# Amplifier.net
KiCad netlist of a schematic drawn in EAGLE
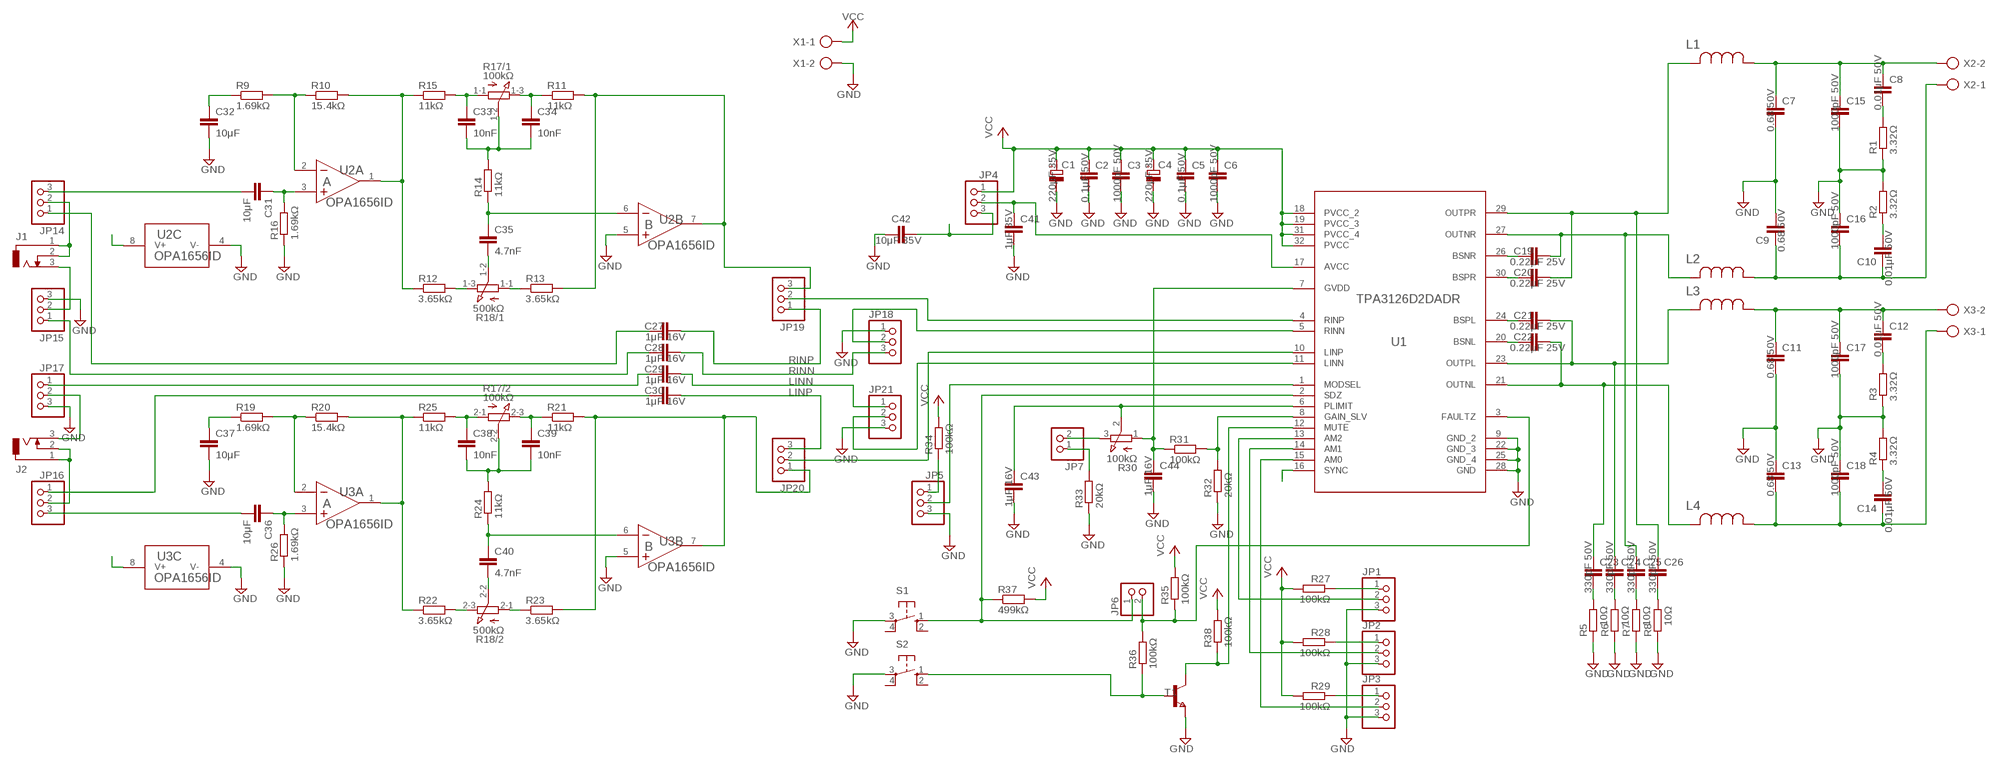
[diagram p0: schematic, sheet 1]

(export (version "E")
  (design (tool "Eeschema 10.0.6"))
  (components
    (comp (ref "C1")
      (value "220μF 35V")
      (footprint "eagle-import:E3,5-10")
      (libsource (lib "eagle-import") (part "CPOL-EUE3.5-10"))
    )
    (comp (ref "C2")
      (value "0.1μF 50V")
      (footprint "eagle-import:C0805")
      (libsource (lib "eagle-import") (part "C-EUC0805"))
    )
    (comp (ref "C3")
      (value "1000pF 50V")
      (footprint "eagle-import:C0805")
      (libsource (lib "eagle-import") (part "C-EUC0805"))
    )
    (comp (ref "C4")
      (value "220μF 35V")
      (footprint "eagle-import:E3,5-10")
      (libsource (lib "eagle-import") (part "CPOL-EUE3.5-10"))
    )
    (comp (ref "C5")
      (value "0.1μF 50V")
      (footprint "eagle-import:C0805")
      (libsource (lib "eagle-import") (part "C-EUC0805"))
    )
    (comp (ref "C6")
      (value "1000pF 50V")
      (footprint "eagle-import:C0805")
      (libsource (lib "eagle-import") (part "C-EUC0805"))
    )
    (comp (ref "C7")
      (value "0.68 50V")
      (footprint "eagle-import:C0805")
      (libsource (lib "eagle-import") (part "C-EUC0805"))
    )
    (comp (ref "C8")
      (value "0.01μF 50V")
      (footprint "eagle-import:C0805")
      (libsource (lib "eagle-import") (part "C-EUC0805"))
    )
    (comp (ref "C9")
      (value "0.68 50V")
      (footprint "eagle-import:C0805")
      (libsource (lib "eagle-import") (part "C-EUC0805"))
    )
    (comp (ref "C10")
      (value "0.01μF 50V")
      (footprint "eagle-import:C0805")
      (libsource (lib "eagle-import") (part "C-EUC0805"))
    )
    (comp (ref "C11")
      (value "0.68 50V")
      (footprint "eagle-import:C0805")
      (libsource (lib "eagle-import") (part "C-EUC0805"))
    )
    (comp (ref "C12")
      (value "0.01μF 50V")
      (footprint "eagle-import:C0805")
      (libsource (lib "eagle-import") (part "C-EUC0805"))
    )
    (comp (ref "C13")
      (value "0.68 50V")
      (footprint "eagle-import:C0805")
      (libsource (lib "eagle-import") (part "C-EUC0805"))
    )
    (comp (ref "C14")
      (value "0.01μF 50V")
      (footprint "eagle-import:C0805")
      (libsource (lib "eagle-import") (part "C-EUC0805"))
    )
    (comp (ref "C15")
      (value "1000pF 50V")
      (footprint "eagle-import:C0603")
      (libsource (lib "eagle-import") (part "C-EUC0603"))
    )
    (comp (ref "C16")
      (value "1000pF 50V")
      (footprint "eagle-import:C0603")
      (libsource (lib "eagle-import") (part "C-EUC0603"))
    )
    (comp (ref "C17")
      (value "1000pF 50V")
      (footprint "eagle-import:C0603")
      (libsource (lib "eagle-import") (part "C-EUC0603"))
    )
    (comp (ref "C18")
      (value "1000pF 50V")
      (footprint "eagle-import:C0603")
      (libsource (lib "eagle-import") (part "C-EUC0603"))
    )
    (comp (ref "C19")
      (value "0.22μF 25V")
      (footprint "eagle-import:C0603")
      (libsource (lib "eagle-import") (part "C-EUC0603"))
    )
    (comp (ref "C20")
      (value "0.22μF 25V")
      (footprint "eagle-import:C0603")
      (libsource (lib "eagle-import") (part "C-EUC0603"))
    )
    (comp (ref "C21")
      (value "0.22μF 25V")
      (footprint "eagle-import:C0603")
      (libsource (lib "eagle-import") (part "C-EUC0603"))
    )
    (comp (ref "C22")
      (value "0.22μF 25V")
      (footprint "eagle-import:C0603")
      (libsource (lib "eagle-import") (part "C-EUC0603"))
    )
    (comp (ref "C23")
      (value "330pF 50V")
      (footprint "eagle-import:C0603")
      (libsource (lib "eagle-import") (part "C-EUC0603"))
    )
    (comp (ref "C24")
      (value "330pF 50V")
      (footprint "eagle-import:C0603")
      (libsource (lib "eagle-import") (part "C-EUC0603"))
    )
    (comp (ref "C25")
      (value "330pF 50V")
      (footprint "eagle-import:C0603")
      (libsource (lib "eagle-import") (part "C-EUC0603"))
    )
    (comp (ref "C26")
      (value "330pF 50V")
      (footprint "eagle-import:C0603")
      (libsource (lib "eagle-import") (part "C-EUC0603"))
    )
    (comp (ref "C27")
      (value "1μF 16V")
      (footprint "eagle-import:C0805")
      (libsource (lib "eagle-import") (part "C-EUC0805"))
    )
    (comp (ref "C28")
      (value "1μF 16V")
      (footprint "eagle-import:C0805")
      (libsource (lib "eagle-import") (part "C-EUC0805"))
    )
    (comp (ref "C29")
      (value "1μF 16V")
      (footprint "eagle-import:C0805")
      (libsource (lib "eagle-import") (part "C-EUC0805"))
    )
    (comp (ref "C30")
      (value "1μF 16V")
      (footprint "eagle-import:C0805")
      (libsource (lib "eagle-import") (part "C-EUC0805"))
    )
    (comp (ref "C31")
      (value "10μF")
      (footprint "eagle-import:C0805")
      (libsource (lib "eagle-import") (part "C-EUC0805"))
    )
    (comp (ref "C32")
      (value "10μF")
      (footprint "eagle-import:C0805")
      (libsource (lib "eagle-import") (part "C-EUC0805"))
    )
    (comp (ref "C33")
      (value "10nF")
      (footprint "eagle-import:C0603")
      (libsource (lib "eagle-import") (part "C-EUC0603"))
    )
    (comp (ref "C34")
      (value "10nF")
      (footprint "eagle-import:C0603")
      (libsource (lib "eagle-import") (part "C-EUC0603"))
    )
    (comp (ref "C35")
      (value "4.7nF")
      (footprint "eagle-import:C0603")
      (libsource (lib "eagle-import") (part "C-EUC0603"))
    )
    (comp (ref "C36")
      (value "10μF")
      (footprint "eagle-import:C0805")
      (libsource (lib "eagle-import") (part "C-EUC0805"))
    )
    (comp (ref "C37")
      (value "10μF")
      (footprint "eagle-import:C0805")
      (libsource (lib "eagle-import") (part "C-EUC0805"))
    )
    (comp (ref "C38")
      (value "10nF")
      (footprint "eagle-import:C0603")
      (libsource (lib "eagle-import") (part "C-EUC0603"))
    )
    (comp (ref "C39")
      (value "10nF")
      (footprint "eagle-import:C0603")
      (libsource (lib "eagle-import") (part "C-EUC0603"))
    )
    (comp (ref "C40")
      (value "4.7nF")
      (footprint "eagle-import:C0603")
      (libsource (lib "eagle-import") (part "C-EUC0603"))
    )
    (comp (ref "C41")
      (value "1μF 35V")
      (footprint "eagle-import:C0603")
      (libsource (lib "eagle-import") (part "C-EUC0603"))
    )
    (comp (ref "C42")
      (value "10μF 35V")
      (footprint "eagle-import:C1210")
      (libsource (lib "eagle-import") (part "C-EUC1210"))
    )
    (comp (ref "C43")
      (value "1μF 16V")
      (footprint "eagle-import:C0805")
      (libsource (lib "eagle-import") (part "C-EUC0805"))
    )
    (comp (ref "C44")
      (value "1μF 16V")
      (footprint "eagle-import:C0805")
      (libsource (lib "eagle-import") (part "C-EUC0805"))
    )
    (comp (ref "J1")
      (value "DCJ0303")
      (footprint "eagle-import:DCJ0303")
      (libsource (lib "eagle-import") (part "DCJ0303"))
    )
    (comp (ref "J2")
      (value "DCJ0303")
      (footprint "eagle-import:DCJ0303")
      (libsource (lib "eagle-import") (part "DCJ0303"))
    )
    (comp (ref "JP1")
      (value "PINHD-1X3")
      (footprint "eagle-import:1X03")
      (libsource (lib "eagle-import") (part "PINHD-1X3"))
    )
    (comp (ref "JP2")
      (value "PINHD-1X3")
      (footprint "eagle-import:1X03")
      (libsource (lib "eagle-import") (part "PINHD-1X3"))
    )
    (comp (ref "JP3")
      (value "PINHD-1X3")
      (footprint "eagle-import:1X03")
      (libsource (lib "eagle-import") (part "PINHD-1X3"))
    )
    (comp (ref "JP4")
      (value "PINHD-1X3")
      (footprint "eagle-import:1X03")
      (libsource (lib "eagle-import") (part "PINHD-1X3"))
    )
    (comp (ref "JP5")
      (value "PINHD-1X3")
      (footprint "eagle-import:1X03")
      (libsource (lib "eagle-import") (part "PINHD-1X3"))
    )
    (comp (ref "JP6")
      (value "PINHD-1X2")
      (footprint "eagle-import:1X02")
      (libsource (lib "eagle-import") (part "PINHD-1X2"))
    )
    (comp (ref "JP7")
      (value "PINHD-1X2")
      (footprint "eagle-import:1X02")
      (libsource (lib "eagle-import") (part "PINHD-1X2"))
    )
    (comp (ref "JP14")
      (value "PINHD-1X3")
      (footprint "eagle-import:1X03")
      (libsource (lib "eagle-import") (part "PINHD-1X3"))
    )
    (comp (ref "JP15")
      (value "PINHD-1X3")
      (footprint "eagle-import:1X03")
      (libsource (lib "eagle-import") (part "PINHD-1X3"))
    )
    (comp (ref "JP16")
      (value "PINHD-1X3")
      (footprint "eagle-import:1X03")
      (libsource (lib "eagle-import") (part "PINHD-1X3"))
    )
    (comp (ref "JP17")
      (value "PINHD-1X3")
      (footprint "eagle-import:1X03")
      (libsource (lib "eagle-import") (part "PINHD-1X3"))
    )
    (comp (ref "JP18")
      (value "PINHD-1X3")
      (footprint "eagle-import:1X03")
      (libsource (lib "eagle-import") (part "PINHD-1X3"))
    )
    (comp (ref "JP19")
      (value "PINHD-1X3")
      (footprint "eagle-import:1X03")
      (libsource (lib "eagle-import") (part "PINHD-1X3"))
    )
    (comp (ref "JP20")
      (value "PINHD-1X3")
      (footprint "eagle-import:1X03")
      (libsource (lib "eagle-import") (part "PINHD-1X3"))
    )
    (comp (ref "JP21")
      (value "PINHD-1X3")
      (footprint "eagle-import:1X03")
      (libsource (lib "eagle-import") (part "PINHD-1X3"))
    )
    (comp (ref "L1")
      (value "7447709100")
      (footprint "eagle-import:IND_1210-WE-PD_WRE")
      (fields (field (name "COPYRIGHT") "Copyright (C) 2023 Ultra Librarian. All rights reserved."))
      (libsource (lib "eagle-import") (part "7447709100"))
    )
    (comp (ref "L2")
      (value "7447709100")
      (footprint "eagle-import:IND_1210-WE-PD_WRE")
      (fields (field (name "COPYRIGHT") "Copyright (C) 2023 Ultra Librarian. All rights reserved."))
      (libsource (lib "eagle-import") (part "7447709100"))
    )
    (comp (ref "L3")
      (value "7447709100")
      (footprint "eagle-import:IND_1210-WE-PD_WRE")
      (fields (field (name "COPYRIGHT") "Copyright (C) 2023 Ultra Librarian. All rights reserved."))
      (libsource (lib "eagle-import") (part "7447709100"))
    )
    (comp (ref "L4")
      (value "7447709100")
      (footprint "eagle-import:IND_1210-WE-PD_WRE")
      (fields (field (name "COPYRIGHT") "Copyright (C) 2023 Ultra Librarian. All rights reserved."))
      (libsource (lib "eagle-import") (part "7447709100"))
    )
    (comp (ref "R1")
      (value "3.32Ω")
      (footprint "eagle-import:R0603")
      (libsource (lib "eagle-import") (part "R-EU_R0603"))
    )
    (comp (ref "R2")
      (value "3.32Ω")
      (footprint "eagle-import:R0603")
      (libsource (lib "eagle-import") (part "R-EU_R0603"))
    )
    (comp (ref "R3")
      (value "3.32Ω")
      (footprint "eagle-import:R0603")
      (libsource (lib "eagle-import") (part "R-EU_R0603"))
    )
    (comp (ref "R4")
      (value "3.32Ω")
      (footprint "eagle-import:R0603")
      (libsource (lib "eagle-import") (part "R-EU_R0603"))
    )
    (comp (ref "R5")
      (value "10Ω")
      (footprint "eagle-import:R0805")
      (libsource (lib "eagle-import") (part "R-EU_R0805"))
    )
    (comp (ref "R6")
      (value "10Ω")
      (footprint "eagle-import:R0805")
      (libsource (lib "eagle-import") (part "R-EU_R0805"))
    )
    (comp (ref "R7")
      (value "10Ω")
      (footprint "eagle-import:R0805")
      (libsource (lib "eagle-import") (part "R-EU_R0805"))
    )
    (comp (ref "R8")
      (value "10Ω")
      (footprint "eagle-import:R0805")
      (libsource (lib "eagle-import") (part "R-EU_R0805"))
    )
    (comp (ref "R9")
      (value "1.69kΩ")
      (footprint "eagle-import:R1206")
      (libsource (lib "eagle-import") (part "R-EU_R1206"))
    )
    (comp (ref "R10")
      (value "15.4kΩ")
      (footprint "eagle-import:R1206")
      (libsource (lib "eagle-import") (part "R-EU_R1206"))
    )
    (comp (ref "R11")
      (value "11kΩ")
      (footprint "eagle-import:R1206")
      (libsource (lib "eagle-import") (part "R-EU_R1206"))
    )
    (comp (ref "R12")
      (value "3.65kΩ")
      (footprint "eagle-import:R1206")
      (libsource (lib "eagle-import") (part "R-EU_R1206"))
    )
    (comp (ref "R13")
      (value "3.65kΩ")
      (footprint "eagle-import:R1206")
      (libsource (lib "eagle-import") (part "R-EU_R1206"))
    )
    (comp (ref "R14")
      (value "11kΩ")
      (footprint "eagle-import:R1206")
      (libsource (lib "eagle-import") (part "R-EU_R1206"))
    )
    (comp (ref "R15")
      (value "11kΩ")
      (footprint "eagle-import:R1206")
      (libsource (lib "eagle-import") (part "R-EU_R1206"))
    )
    (comp (ref "R16")
      (value "1.69kΩ")
      (footprint "eagle-import:R1206")
      (libsource (lib "eagle-import") (part "R-EU_R1206"))
    )
    (comp (ref "R17")
      (value "100kΩ")
      (footprint "eagle-import:3RP_1610G")
      (libsource (lib "eagle-import") (part "3RP/1610G"))
    )
    (comp (ref "R18")
      (value "500kΩ")
      (footprint "eagle-import:3RP_1610G")
      (libsource (lib "eagle-import") (part "3RP/1610G"))
    )
    (comp (ref "R19")
      (value "1.69kΩ")
      (footprint "eagle-import:R1206")
      (libsource (lib "eagle-import") (part "R-EU_R1206"))
    )
    (comp (ref "R20")
      (value "15.4kΩ")
      (footprint "eagle-import:R1206")
      (libsource (lib "eagle-import") (part "R-EU_R1206"))
    )
    (comp (ref "R21")
      (value "11kΩ")
      (footprint "eagle-import:R1206")
      (libsource (lib "eagle-import") (part "R-EU_R1206"))
    )
    (comp (ref "R22")
      (value "3.65kΩ")
      (footprint "eagle-import:R1206")
      (libsource (lib "eagle-import") (part "R-EU_R1206"))
    )
    (comp (ref "R23")
      (value "3.65kΩ")
      (footprint "eagle-import:R1206")
      (libsource (lib "eagle-import") (part "R-EU_R1206"))
    )
    (comp (ref "R24")
      (value "11kΩ")
      (footprint "eagle-import:R1206")
      (libsource (lib "eagle-import") (part "R-EU_R1206"))
    )
    (comp (ref "R25")
      (value "11kΩ")
      (footprint "eagle-import:R1206")
      (libsource (lib "eagle-import") (part "R-EU_R1206"))
    )
    (comp (ref "R26")
      (value "1.69kΩ")
      (footprint "eagle-import:R1206")
      (libsource (lib "eagle-import") (part "R-EU_R1206"))
    )
    (comp (ref "R27")
      (value "100kΩ")
      (footprint "eagle-import:M0805")
      (libsource (lib "eagle-import") (part "R-EU_M0805"))
    )
    (comp (ref "R28")
      (value "100kΩ")
      (footprint "eagle-import:M0805")
      (libsource (lib "eagle-import") (part "R-EU_M0805"))
    )
    (comp (ref "R29")
      (value "100kΩ")
      (footprint "eagle-import:M0805")
      (libsource (lib "eagle-import") (part "R-EU_M0805"))
    )
    (comp (ref "R30")
      (value "100kΩ")
      (footprint "eagle-import:3RP_1610N")
      (libsource (lib "eagle-import") (part "3RP/1610N"))
    )
    (comp (ref "R31")
      (value "100kΩ")
      (footprint "eagle-import:R0805")
      (libsource (lib "eagle-import") (part "R-EU_R0805"))
    )
    (comp (ref "R32")
      (value "20kΩ")
      (footprint "eagle-import:R0805")
      (libsource (lib "eagle-import") (part "R-EU_R0805"))
    )
    (comp (ref "R33")
      (value "20kΩ")
      (footprint "eagle-import:R0805")
      (libsource (lib "eagle-import") (part "R-EU_R0805"))
    )
    (comp (ref "R34")
      (value "100kΩ")
      (footprint "eagle-import:R0805")
      (libsource (lib "eagle-import") (part "R-EU_R0805"))
    )
    (comp (ref "R35")
      (value "100kΩ")
      (footprint "eagle-import:R0805")
      (libsource (lib "eagle-import") (part "R-EU_R0805"))
    )
    (comp (ref "R36")
      (value "100kΩ")
      (footprint "eagle-import:R0805")
      (libsource (lib "eagle-import") (part "R-EU_R0805"))
    )
    (comp (ref "R37")
      (value "499kΩ")
      (footprint "eagle-import:R0805")
      (libsource (lib "eagle-import") (part "R-EU_R0805"))
    )
    (comp (ref "R38")
      (value "100kΩ")
      (footprint "eagle-import:R0805")
      (libsource (lib "eagle-import") (part "R-EU_R0805"))
    )
    (comp (ref "S1")
      (value "10-XX")
      (footprint "eagle-import:B3F-10XX")
      (fields (field (name "MPN") "B3F-1000"))
      (libsource (lib "eagle-import") (part "10-XX"))
    )
    (comp (ref "S2")
      (value "10-XX")
      (footprint "eagle-import:B3F-10XX")
      (fields (field (name "MPN") "B3F-1000"))
      (libsource (lib "eagle-import") (part "10-XX"))
    )
    (comp (ref "T1")
      (value "NPNSOT23")
      (footprint "eagle-import:SOT-23")
      (fields (field (name "MPN") "DSS20201L-7"))
      (libsource (lib "eagle-import") (part "NPNSOT23"))
    )
    (comp (ref "U1")
      (value "TPA3126D2DADR")
      (footprint "eagle-import:DAD0032A_N")
      (fields (field (name "COPYRIGHT") "Copyright (C) 2023 Ultra Librarian. All rights reserved."))
      (libsource (lib "eagle-import") (part "TPA3126D2DADR"))
    )
    (comp (ref "U2")
      (value "OPA1656ID")
      (footprint "eagle-import:D0008A_N")
      (fields (field (name "COPYRIGHT") "Copyright (C) 2023 Ultra Librarian. All rights reserved."))
      (libsource (lib "eagle-import") (part "OPA1656ID"))
    )
    (comp (ref "U3")
      (value "OPA1656ID")
      (footprint "eagle-import:D0008A_N")
      (fields (field (name "COPYRIGHT") "Copyright (C) 2023 Ultra Librarian. All rights reserved."))
      (libsource (lib "eagle-import") (part "OPA1656ID"))
    )
    (comp (ref "X1")
      (value "AK500/2")
      (footprint "eagle-import:AK500_2")
      (libsource (lib "eagle-import") (part "AK500/2"))
    )
    (comp (ref "X2")
      (value "AK500/2")
      (footprint "eagle-import:AK500_2")
      (libsource (lib "eagle-import") (part "AK500/2"))
    )
    (comp (ref "X3")
      (value "AK500/2")
      (footprint "eagle-import:AK500_2")
      (libsource (lib "eagle-import") (part "AK500/2"))
    )
  )
  (nets
    (net (code "1") (name "/LINN") (class "Default")
      (node (ref "C29") (pin "2") (pinfunction "2_2") (pintype "passive"))
      (node (ref "JP21") (pin "1") (pinfunction "1_1") (pintype "passive"))
    )
    (net (code "2") (name "/LINP") (class "Default")
      (node (ref "C30") (pin "1") (pinfunction "1_1") (pintype "passive"))
      (node (ref "C30") (pin "2") (pinfunction "2_2") (pintype "passive"))
      (node (ref "JP16") (pin "1") (pinfunction "1_1") (pintype "passive"))
      (node (ref "JP20") (pin "3") (pinfunction "3_3") (pintype "passive"))
    )
    (net (code "3") (name "/RINN") (class "Default")
      (node (ref "C28") (pin "1") (pinfunction "1_1") (pintype "passive"))
      (node (ref "C28") (pin "2") (pinfunction "2_2") (pintype "passive"))
      (node (ref "JP15") (pin "1") (pinfunction "1_1") (pintype "passive"))
      (node (ref "JP18") (pin "3") (pinfunction "3_3") (pintype "passive"))
    )
    (net (code "4") (name "/RINP") (class "Default")
      (node (ref "C27") (pin "1") (pinfunction "1_1") (pintype "passive"))
      (node (ref "C27") (pin "2") (pinfunction "2_2") (pintype "passive"))
      (node (ref "JP14") (pin "1") (pinfunction "1_1") (pintype "passive"))
      (node (ref "JP19") (pin "1") (pinfunction "1_1") (pintype "passive"))
    )
    (net (code "5") (name "GND") (class "Default")
      (node (ref "C1") (pin "-") (pinfunction "-_-") (pintype "passive"))
      (node (ref "C11") (pin "2") (pinfunction "2_2") (pintype "passive"))
      (node (ref "C13") (pin "1") (pinfunction "1_1") (pintype "passive"))
      (node (ref "C15") (pin "2") (pinfunction "2_2") (pintype "passive"))
      (node (ref "C16") (pin "1") (pinfunction "1_1") (pintype "passive"))
      (node (ref "C17") (pin "2") (pinfunction "2_2") (pintype "passive"))
      (node (ref "C18") (pin "1") (pinfunction "1_1") (pintype "passive"))
      (node (ref "C2") (pin "2") (pinfunction "2_2") (pintype "passive"))
      (node (ref "C3") (pin "2") (pinfunction "2_2") (pintype "passive"))
      (node (ref "C32") (pin "2") (pinfunction "2_2") (pintype "passive"))
      (node (ref "C37") (pin "2") (pinfunction "2_2") (pintype "passive"))
      (node (ref "C4") (pin "-") (pinfunction "-_-") (pintype "passive"))
      (node (ref "C41") (pin "2") (pinfunction "2_2") (pintype "passive"))
      (node (ref "C42") (pin "1") (pinfunction "1_1") (pintype "passive"))
      (node (ref "C43") (pin "2") (pinfunction "2_2") (pintype "passive"))
      (node (ref "C44") (pin "2") (pinfunction "2_2") (pintype "passive"))
      (node (ref "C5") (pin "2") (pinfunction "2_2") (pintype "passive"))
      (node (ref "C6") (pin "2") (pinfunction "2_2") (pintype "passive"))
      (node (ref "C7") (pin "2") (pinfunction "2_2") (pintype "passive"))
      (node (ref "C9") (pin "2") (pinfunction "2_2") (pintype "passive"))
      (node (ref "JP1") (pin "3") (pinfunction "3_3") (pintype "passive"))
      (node (ref "JP15") (pin "3") (pinfunction "3_3") (pintype "passive"))
      (node (ref "JP17") (pin "3") (pinfunction "3_3") (pintype "passive"))
      (node (ref "JP18") (pin "1") (pinfunction "1_1") (pintype "passive"))
      (node (ref "JP2") (pin "3") (pinfunction "3_3") (pintype "passive"))
      (node (ref "JP21") (pin "3") (pinfunction "3_3") (pintype "passive"))
      (node (ref "JP3") (pin "3") (pinfunction "3_3") (pintype "passive"))
      (node (ref "JP5") (pin "3") (pinfunction "3_3") (pintype "passive"))
      (node (ref "R1") (pin "1") (pinfunction "1_1") (pintype "passive"))
      (node (ref "R16") (pin "1") (pinfunction "1_1") (pintype "passive"))
      (node (ref "R2") (pin "2") (pinfunction "2_2") (pintype "passive"))
      (node (ref "R26") (pin "1") (pinfunction "1_1") (pintype "passive"))
      (node (ref "R3") (pin "1") (pinfunction "1_1") (pintype "passive"))
      (node (ref "R32") (pin "1") (pinfunction "1_1") (pintype "passive"))
      (node (ref "R33") (pin "1") (pinfunction "1_1") (pintype "passive"))
      (node (ref "R4") (pin "2") (pinfunction "2_2") (pintype "passive"))
      (node (ref "R5") (pin "1") (pinfunction "1_1") (pintype "passive"))
      (node (ref "R6") (pin "1") (pinfunction "1_1") (pintype "passive"))
      (node (ref "R7") (pin "1") (pinfunction "1_1") (pintype "passive"))
      (node (ref "R8") (pin "1") (pinfunction "1_1") (pintype "passive"))
      (node (ref "S1") (pin "3") (pinfunction "P_3") (pintype "passive"))
      (node (ref "S2") (pin "3") (pinfunction "P_3") (pintype "passive"))
      (node (ref "T1") (pin "2") (pinfunction "E_2") (pintype "passive"))
      (node (ref "U1") (pin "22") (pinfunction "GND_3_22") (pintype "power_in"))
      (node (ref "U1") (pin "25") (pinfunction "GND_4_25") (pintype "power_in"))
      (node (ref "U1") (pin "28") (pinfunction "GND_28") (pintype "power_in"))
      (node (ref "U1") (pin "9") (pinfunction "GND_2_9") (pintype "power_in"))
      (node (ref "U2") (pin "4") (pinfunction "V-_4") (pintype "power_in"))
      (node (ref "U2") (pin "5") (pinfunction "IN+_5") (pintype "input"))
      (node (ref "U3") (pin "4") (pinfunction "V-_4") (pintype "power_in"))
      (node (ref "U3") (pin "5") (pinfunction "IN+_5") (pintype "input"))
      (node (ref "X1") (pin "2") (pinfunction "KL_2") (pintype "passive"))
    )
    (net (code "6") (name "Net-(C8-Pad2)") (class "Default")
      (node (ref "C8") (pin "2") (pinfunction "2_2") (pintype "passive"))
      (node (ref "R1") (pin "2") (pinfunction "2_2") (pintype "passive"))
    )
    (net (code "7") (name "Net-(C10-Pad2)") (class "Default")
      (node (ref "C10") (pin "2") (pinfunction "2_2") (pintype "passive"))
      (node (ref "R2") (pin "1") (pinfunction "1_1") (pintype "passive"))
    )
    (net (code "8") (name "Net-(C12-Pad2)") (class "Default")
      (node (ref "C12") (pin "2") (pinfunction "2_2") (pintype "passive"))
      (node (ref "R3") (pin "2") (pinfunction "2_2") (pintype "passive"))
    )
    (net (code "9") (name "Net-(C14-Pad2)") (class "Default")
      (node (ref "C14") (pin "2") (pinfunction "2_2") (pintype "passive"))
      (node (ref "R4") (pin "1") (pinfunction "1_1") (pintype "passive"))
    )
    (net (code "10") (name "Net-(C23-Pad2)") (class "Default")
      (node (ref "C23") (pin "2") (pinfunction "2_2") (pintype "passive"))
      (node (ref "R5") (pin "2") (pinfunction "2_2") (pintype "passive"))
    )
    (net (code "11") (name "Net-(C24-Pad2)") (class "Default")
      (node (ref "C24") (pin "2") (pinfunction "2_2") (pintype "passive"))
      (node (ref "R6") (pin "2") (pinfunction "2_2") (pintype "passive"))
    )
    (net (code "12") (name "Net-(C25-Pad2)") (class "Default")
      (node (ref "C25") (pin "2") (pinfunction "2_2") (pintype "passive"))
      (node (ref "R7") (pin "2") (pinfunction "2_2") (pintype "passive"))
    )
    (net (code "13") (name "Net-(C26-Pad2)") (class "Default")
      (node (ref "C26") (pin "2") (pinfunction "2_2") (pintype "passive"))
      (node (ref "R8") (pin "2") (pinfunction "2_2") (pintype "passive"))
    )
    (net (code "14") (name "Net-(C29-Pad1)") (class "Default")
      (node (ref "C29") (pin "1") (pinfunction "1_1") (pintype "passive"))
      (node (ref "JP17") (pin "1") (pinfunction "1_1") (pintype "passive"))
    )
    (net (code "15") (name "Net-(C31-Pad2)") (class "Default")
      (node (ref "C31") (pin "2") (pinfunction "2_2") (pintype "passive"))
      (node (ref "JP14") (pin "3") (pinfunction "3_3") (pintype "passive"))
    )
    (net (code "16") (name "Net-(C32-Pad1)") (class "Default")
      (node (ref "C32") (pin "1") (pinfunction "1_1") (pintype "passive"))
      (node (ref "R9") (pin "1") (pinfunction "1_1") (pintype "passive"))
    )
    (net (code "17") (name "Net-(C36-Pad2)") (class "Default")
      (node (ref "C36") (pin "2") (pinfunction "2_2") (pintype "passive"))
      (node (ref "JP16") (pin "3") (pinfunction "3_3") (pintype "passive"))
    )
    (net (code "18") (name "Net-(C37-Pad1)") (class "Default")
      (node (ref "C37") (pin "1") (pinfunction "1_1") (pintype "passive"))
      (node (ref "R19") (pin "1") (pinfunction "1_1") (pintype "passive"))
    )
    (net (code "19") (name "Net-(C42-Pad2)") (class "Default")
      (node (ref "C42") (pin "2") (pinfunction "2_2") (pintype "passive"))
      (node (ref "JP4") (pin "3") (pinfunction "3_3") (pintype "passive"))
    )
    (net (code "20") (name "Net-(J1-Pad1)") (class "Default")
      (node (ref "J1") (pin "1") (pinfunction "1_1") (pintype "passive"))
      (node (ref "J1") (pin "2") (pinfunction "2_2") (pintype "passive"))
      (node (ref "JP14") (pin "2") (pinfunction "2_2") (pintype "passive"))
    )
    (net (code "21") (name "Net-(J1-Pad3)") (class "Default")
      (node (ref "J1") (pin "3") (pinfunction "3_3") (pintype "passive"))
      (node (ref "JP15") (pin "2") (pinfunction "2_2") (pintype "passive"))
    )
    (net (code "22") (name "Net-(J2-Pad1)") (class "Default")
      (node (ref "J2") (pin "1") (pinfunction "1_1") (pintype "passive"))
      (node (ref "J2") (pin "2") (pinfunction "2_2") (pintype "passive"))
      (node (ref "JP16") (pin "2") (pinfunction "2_2") (pintype "passive"))
    )
    (net (code "23") (name "Net-(J2-Pad3)") (class "Default")
      (node (ref "J2") (pin "3") (pinfunction "3_3") (pintype "passive"))
      (node (ref "JP17") (pin "2") (pinfunction "2_2") (pintype "passive"))
    )
    (net (code "24") (name "Net-(JP1-Pad1)") (class "Default")
      (node (ref "JP1") (pin "1") (pinfunction "1_1") (pintype "passive"))
      (node (ref "R27") (pin "1") (pinfunction "1_1") (pintype "passive"))
    )
    (net (code "25") (name "Net-(JP2-Pad1)") (class "Default")
      (node (ref "JP2") (pin "1") (pinfunction "1_1") (pintype "passive"))
      (node (ref "R28") (pin "1") (pinfunction "1_1") (pintype "passive"))
    )
    (net (code "26") (name "Net-(JP3-Pad1)") (class "Default")
      (node (ref "JP3") (pin "1") (pinfunction "1_1") (pintype "passive"))
      (node (ref "R29") (pin "1") (pinfunction "1_1") (pintype "passive"))
    )
    (net (code "27") (name "Net-(JP5-Pad1)") (class "Default")
      (node (ref "JP5") (pin "1") (pinfunction "1_1") (pintype "passive"))
      (node (ref "R34") (pin "1") (pinfunction "1_1") (pintype "passive"))
    )
    (net (code "28") (name "Net-(JP7-Pad1)") (class "Default")
      (node (ref "JP7") (pin "1") (pinfunction "1_1") (pintype "passive"))
      (node (ref "R33") (pin "2") (pinfunction "2_2") (pintype "passive"))
    )
    (net (code "29") (name "Net-(R17A-A)") (class "Default")
      (node (ref "C33") (pin "1") (pinfunction "1_1") (pintype "passive"))
      (node (ref "R15") (pin "2") (pinfunction "2_2") (pintype "passive"))
      (node (ref "R17") (pin "1-1") (pinfunction "A_1-1") (pintype "passive"))
    )
    (net (code "30") (name "Net-(R17A-E)") (class "Default")
      (node (ref "C34") (pin "1") (pinfunction "1_1") (pintype "passive"))
      (node (ref "R11") (pin "1") (pinfunction "1_1") (pintype "passive"))
      (node (ref "R17") (pin "1-3") (pinfunction "E_1-3") (pintype "passive"))
    )
    (net (code "31") (name "Net-(R17A-S)") (class "Default")
      (node (ref "C33") (pin "2") (pinfunction "2_2") (pintype "passive"))
      (node (ref "C34") (pin "2") (pinfunction "2_2") (pintype "passive"))
      (node (ref "R14") (pin "2") (pinfunction "2_2") (pintype "passive"))
      (node (ref "R17") (pin "1-2") (pinfunction "S_1-2") (pintype "passive"))
    )
    (net (code "32") (name "Net-(R17B-A)") (class "Default")
      (node (ref "C38") (pin "1") (pinfunction "1_1") (pintype "passive"))
      (node (ref "R17") (pin "2-1") (pinfunction "A_2-1") (pintype "passive"))
      (node (ref "R25") (pin "2") (pinfunction "2_2") (pintype "passive"))
    )
    (net (code "33") (name "Net-(R17B-E)") (class "Default")
      (node (ref "C39") (pin "1") (pinfunction "1_1") (pintype "passive"))
      (node (ref "R17") (pin "2-3") (pinfunction "E_2-3") (pintype "passive"))
      (node (ref "R21") (pin "1") (pinfunction "1_1") (pintype "passive"))
    )
    (net (code "34") (name "Net-(R17B-S)") (class "Default")
      (node (ref "C38") (pin "2") (pinfunction "2_2") (pintype "passive"))
      (node (ref "C39") (pin "2") (pinfunction "2_2") (pintype "passive"))
      (node (ref "R17") (pin "2-2") (pinfunction "S_2-2") (pintype "passive"))
      (node (ref "R24") (pin "2") (pinfunction "2_2") (pintype "passive"))
    )
    (net (code "35") (name "Net-(R18A-A)") (class "Default")
      (node (ref "R13") (pin "1") (pinfunction "1_1") (pintype "passive"))
      (node (ref "R18") (pin "1-1") (pinfunction "A_1-1") (pintype "passive"))
    )
    (net (code "36") (name "Net-(R18A-E)") (class "Default")
      (node (ref "R12") (pin "2") (pinfunction "2_2") (pintype "passive"))
      (node (ref "R18") (pin "1-3") (pinfunction "E_1-3") (pintype "passive"))
    )
    (net (code "37") (name "Net-(R18A-S)") (class "Default")
      (node (ref "C35") (pin "2") (pinfunction "2_2") (pintype "passive"))
      (node (ref "R18") (pin "1-2") (pinfunction "S_1-2") (pintype "passive"))
    )
    (net (code "38") (name "Net-(R18B-A)") (class "Default")
      (node (ref "R18") (pin "2-1") (pinfunction "A_2-1") (pintype "passive"))
      (node (ref "R23") (pin "1") (pinfunction "1_1") (pintype "passive"))
    )
    (net (code "39") (name "Net-(R18B-E)") (class "Default")
      (node (ref "R18") (pin "2-3") (pinfunction "E_2-3") (pintype "passive"))
      (node (ref "R22") (pin "2") (pinfunction "2_2") (pintype "passive"))
    )
    (net (code "40") (name "Net-(R18B-S)") (class "Default")
      (node (ref "C40") (pin "2") (pinfunction "2_2") (pintype "passive"))
      (node (ref "R18") (pin "2-2") (pinfunction "S_2-2") (pintype "passive"))
    )
    (net (code "41") (name "Net-(R30-A)") (class "Default")
      (node (ref "C44") (pin "1") (pinfunction "1_1") (pintype "passive"))
      (node (ref "R30") (pin "1") (pinfunction "A_1") (pintype "passive"))
      (node (ref "R31") (pin "1") (pinfunction "1_1") (pintype "passive"))
      (node (ref "U1") (pin "7") (pinfunction "GVDD_7") (pintype "passive"))
    )
    (net (code "42") (name "Net-(R30-E)") (class "Default")
      (node (ref "JP7") (pin "2") (pinfunction "2_2") (pintype "passive"))
      (node (ref "R30") (pin "3") (pinfunction "E_3") (pintype "passive"))
    )
    (net (code "43") (name "Net-(R30-S)") (class "Default")
      (node (ref "C43") (pin "1") (pinfunction "1_1") (pintype "passive"))
      (node (ref "R30") (pin "2") (pinfunction "S_2") (pintype "passive"))
      (node (ref "U1") (pin "6") (pinfunction "PLIMIT_6") (pintype "input"))
    )
    (net (code "44") (name "Net-(S1-S)") (class "Default")
      (node (ref "JP6") (pin "1") (pinfunction "1_1") (pintype "passive"))
      (node (ref "R37") (pin "1") (pinfunction "1_1") (pintype "passive"))
      (node (ref "S1") (pin "1") (pinfunction "S_1") (pintype "passive"))
      (node (ref "U1") (pin "2") (pinfunction "SDZ_2") (pintype "input"))
    )
    (net (code "45") (name "Net-(S2-S)") (class "Default")
      (node (ref "R36") (pin "1") (pinfunction "1_1") (pintype "passive"))
      (node (ref "S2") (pin "1") (pinfunction "S_1") (pintype "passive"))
      (node (ref "T1") (pin "3") (pinfunction "B_3") (pintype "passive"))
    )
    (net (code "46") (name "Net-(T1-C)") (class "Default")
      (node (ref "R38") (pin "1") (pinfunction "1_1") (pintype "passive"))
      (node (ref "T1") (pin "1") (pinfunction "C_1") (pintype "passive"))
      (node (ref "U1") (pin "12") (pinfunction "MUTE_12") (pintype "input"))
    )
    (net (code "47") (name "Net-(U1-AM0)") (class "Default")
      (node (ref "JP3") (pin "2") (pinfunction "2_2") (pintype "passive"))
      (node (ref "U1") (pin "15") (pinfunction "AM0_15") (pintype "input"))
    )
    (net (code "48") (name "Net-(U1-AM1)") (class "Default")
      (node (ref "JP2") (pin "2") (pinfunction "2_2") (pintype "passive"))
      (node (ref "U1") (pin "14") (pinfunction "AM1_14") (pintype "input"))
    )
    (net (code "49") (name "Net-(U1-AM2)") (class "Default")
      (node (ref "JP1") (pin "2") (pinfunction "2_2") (pintype "passive"))
      (node (ref "U1") (pin "13") (pinfunction "AM2_13") (pintype "input"))
    )
    (net (code "50") (name "Net-(U1-AVCC)") (class "Default")
      (node (ref "C41") (pin "1") (pinfunction "1_1") (pintype "passive"))
      (node (ref "JP4") (pin "2") (pinfunction "2_2") (pintype "passive"))
      (node (ref "U1") (pin "17") (pinfunction "AVCC_17") (pintype "power_in"))
    )
    (net (code "51") (name "Net-(U1-BSNL)") (class "Default")
      (node (ref "C22") (pin "1") (pinfunction "1_1") (pintype "passive"))
      (node (ref "U1") (pin "20") (pinfunction "BSNL_20") (pintype "passive"))
    )
    (net (code "52") (name "Net-(U1-BSNR)") (class "Default")
      (node (ref "C19") (pin "1") (pinfunction "1_1") (pintype "passive"))
      (node (ref "U1") (pin "26") (pinfunction "BSNR_26") (pintype "passive"))
    )
    (net (code "53") (name "Net-(U1-BSPL)") (class "Default")
      (node (ref "C21") (pin "1") (pinfunction "1_1") (pintype "passive"))
      (node (ref "U1") (pin "24") (pinfunction "BSPL_24") (pintype "passive"))
    )
    (net (code "54") (name "Net-(U1-BSPR)") (class "Default")
      (node (ref "C20") (pin "1") (pinfunction "1_1") (pintype "passive"))
      (node (ref "U1") (pin "30") (pinfunction "BSPR_30") (pintype "passive"))
    )
    (net (code "55") (name "Net-(U1-FAULTZ)") (class "Default")
      (node (ref "JP6") (pin "2") (pinfunction "2_2") (pintype "passive"))
      (node (ref "R35") (pin "1") (pinfunction "1_1") (pintype "passive"))
      (node (ref "R36") (pin "2") (pinfunction "2_2") (pintype "passive"))
      (node (ref "U1") (pin "3") (pinfunction "FAULTZ_3") (pintype "output"))
    )
    (net (code "56") (name "Net-(U1-GAIN_SLV)") (class "Default")
      (node (ref "R31") (pin "2") (pinfunction "2_2") (pintype "passive"))
      (node (ref "R32") (pin "2") (pinfunction "2_2") (pintype "passive"))
      (node (ref "U1") (pin "8") (pinfunction "GAIN_SLV_8") (pintype "input"))
    )
    (net (code "57") (name "Net-(U1-LINN)") (class "Default")
      (node (ref "JP21") (pin "2") (pinfunction "2_2") (pintype "passive"))
      (node (ref "U1") (pin "11") (pinfunction "LINN_11") (pintype "input"))
    )
    (net (code "58") (name "Net-(U1-LINP)") (class "Default")
      (node (ref "JP20") (pin "2") (pinfunction "2_2") (pintype "passive"))
      (node (ref "U1") (pin "10") (pinfunction "LINP_10") (pintype "input"))
    )
    (net (code "59") (name "Net-(U1-MODSEL)") (class "Default")
      (node (ref "JP5") (pin "2") (pinfunction "2_2") (pintype "passive"))
      (node (ref "U1") (pin "1") (pinfunction "MODSEL_1") (pintype "input"))
    )
    (net (code "60") (name "Net-(U1-OUTNL)") (class "Default")
      (node (ref "C22") (pin "2") (pinfunction "2_2") (pintype "passive"))
      (node (ref "C23") (pin "1") (pinfunction "1_1") (pintype "passive"))
      (node (ref "L4") (pin "2") (pinfunction "2_2") (pintype "passive"))
      (node (ref "U1") (pin "21") (pinfunction "OUTNL_21") (pintype "tri_state"))
    )
    (net (code "61") (name "Net-(U1-OUTNR)") (class "Default")
      (node (ref "C19") (pin "2") (pinfunction "2_2") (pintype "passive"))
      (node (ref "C25") (pin "1") (pinfunction "1_1") (pintype "passive"))
      (node (ref "L2") (pin "2") (pinfunction "2_2") (pintype "passive"))
      (node (ref "U1") (pin "27") (pinfunction "OUTNR_27") (pintype "tri_state"))
    )
    (net (code "62") (name "Net-(U1-OUTPL)") (class "Default")
      (node (ref "C21") (pin "2") (pinfunction "2_2") (pintype "passive"))
      (node (ref "C24") (pin "1") (pinfunction "1_1") (pintype "passive"))
      (node (ref "L3") (pin "2") (pinfunction "2_2") (pintype "passive"))
      (node (ref "U1") (pin "23") (pinfunction "OUTPL_23") (pintype "tri_state"))
    )
    (net (code "63") (name "Net-(U1-OUTPR)") (class "Default")
      (node (ref "C20") (pin "2") (pinfunction "2_2") (pintype "passive"))
      (node (ref "C26") (pin "1") (pinfunction "1_1") (pintype "passive"))
      (node (ref "L1") (pin "2") (pinfunction "2_2") (pintype "passive"))
      (node (ref "U1") (pin "29") (pinfunction "OUTPR_29") (pintype "tri_state"))
    )
    (net (code "64") (name "Net-(U1-RINN)") (class "Default")
      (node (ref "JP18") (pin "2") (pinfunction "2_2") (pintype "passive"))
      (node (ref "U1") (pin "5") (pinfunction "RINN_5") (pintype "input"))
    )
    (net (code "65") (name "Net-(U1-RINP)") (class "Default")
      (node (ref "JP19") (pin "2") (pinfunction "2_2") (pintype "passive"))
      (node (ref "U1") (pin "4") (pinfunction "RINP_4") (pintype "input"))
    )
    (net (code "66") (name "Net-(U2A-IN+)") (class "Default")
      (node (ref "C31") (pin "1") (pinfunction "1_1") (pintype "passive"))
      (node (ref "R16") (pin "2") (pinfunction "2_2") (pintype "passive"))
      (node (ref "U2") (pin "3") (pinfunction "IN+_3") (pintype "input"))
    )
    (net (code "67") (name "Net-(U2A-IN-)") (class "Default")
      (node (ref "R10") (pin "1") (pinfunction "1_1") (pintype "passive"))
      (node (ref "R9") (pin "2") (pinfunction "2_2") (pintype "passive"))
      (node (ref "U2") (pin "2") (pinfunction "IN-_2") (pintype "input"))
    )
    (net (code "68") (name "Net-(U2A-OUT)") (class "Default")
      (node (ref "R10") (pin "2") (pinfunction "2_2") (pintype "passive"))
      (node (ref "R12") (pin "1") (pinfunction "1_1") (pintype "passive"))
      (node (ref "R15") (pin "1") (pinfunction "1_1") (pintype "passive"))
      (node (ref "U2") (pin "1") (pinfunction "OUT_1") (pintype "output"))
    )
    (net (code "69") (name "Net-(U2B-IN-)") (class "Default")
      (node (ref "C35") (pin "1") (pinfunction "1_1") (pintype "passive"))
      (node (ref "R14") (pin "1") (pinfunction "1_1") (pintype "passive"))
      (node (ref "U2") (pin "6") (pinfunction "IN-_6") (pintype "input"))
    )
    (net (code "70") (name "Net-(U2B-OUT)") (class "Default")
      (node (ref "JP19") (pin "3") (pinfunction "3_3") (pintype "passive"))
      (node (ref "R11") (pin "2") (pinfunction "2_2") (pintype "passive"))
      (node (ref "R13") (pin "2") (pinfunction "2_2") (pintype "passive"))
      (node (ref "U2") (pin "7") (pinfunction "OUT_7") (pintype "output"))
    )
    (net (code "71") (name "Net-(U3A-IN+)") (class "Default")
      (node (ref "C36") (pin "1") (pinfunction "1_1") (pintype "passive"))
      (node (ref "R26") (pin "2") (pinfunction "2_2") (pintype "passive"))
      (node (ref "U3") (pin "3") (pinfunction "IN+_3") (pintype "input"))
    )
    (net (code "72") (name "Net-(U3A-IN-)") (class "Default")
      (node (ref "R19") (pin "2") (pinfunction "2_2") (pintype "passive"))
      (node (ref "R20") (pin "1") (pinfunction "1_1") (pintype "passive"))
      (node (ref "U3") (pin "2") (pinfunction "IN-_2") (pintype "input"))
    )
    (net (code "73") (name "Net-(U3A-OUT)") (class "Default")
      (node (ref "R20") (pin "2") (pinfunction "2_2") (pintype "passive"))
      (node (ref "R22") (pin "1") (pinfunction "1_1") (pintype "passive"))
      (node (ref "R25") (pin "1") (pinfunction "1_1") (pintype "passive"))
      (node (ref "U3") (pin "1") (pinfunction "OUT_1") (pintype "output"))
    )
    (net (code "74") (name "Net-(U3B-IN-)") (class "Default")
      (node (ref "C40") (pin "1") (pinfunction "1_1") (pintype "passive"))
      (node (ref "R24") (pin "1") (pinfunction "1_1") (pintype "passive"))
      (node (ref "U3") (pin "6") (pinfunction "IN-_6") (pintype "input"))
    )
    (net (code "75") (name "Net-(U3B-OUT)") (class "Default")
      (node (ref "JP20") (pin "1") (pinfunction "1_1") (pintype "passive"))
      (node (ref "R21") (pin "2") (pinfunction "2_2") (pintype "passive"))
      (node (ref "R23") (pin "2") (pinfunction "2_2") (pintype "passive"))
      (node (ref "U3") (pin "7") (pinfunction "OUT_7") (pintype "output"))
    )
    (net (code "76") (name "Net-(X2A-KL)") (class "Default")
      (node (ref "C10") (pin "1") (pinfunction "1_1") (pintype "passive"))
      (node (ref "C16") (pin "2") (pinfunction "2_2") (pintype "passive"))
      (node (ref "C9") (pin "1") (pinfunction "1_1") (pintype "passive"))
      (node (ref "L2") (pin "1") (pinfunction "1_1") (pintype "passive"))
      (node (ref "X2") (pin "1") (pinfunction "KL_1") (pintype "passive"))
    )
    (net (code "77") (name "Net-(X2B-KL)") (class "Default")
      (node (ref "C15") (pin "1") (pinfunction "1_1") (pintype "passive"))
      (node (ref "C7") (pin "1") (pinfunction "1_1") (pintype "passive"))
      (node (ref "C8") (pin "1") (pinfunction "1_1") (pintype "passive"))
      (node (ref "L1") (pin "1") (pinfunction "1_1") (pintype "passive"))
      (node (ref "X2") (pin "2") (pinfunction "KL_2") (pintype "passive"))
    )
    (net (code "78") (name "Net-(X3A-KL)") (class "Default")
      (node (ref "C13") (pin "2") (pinfunction "2_2") (pintype "passive"))
      (node (ref "C14") (pin "1") (pinfunction "1_1") (pintype "passive"))
      (node (ref "C18") (pin "2") (pinfunction "2_2") (pintype "passive"))
      (node (ref "L4") (pin "1") (pinfunction "1_1") (pintype "passive"))
      (node (ref "X3") (pin "1") (pinfunction "KL_1") (pintype "passive"))
    )
    (net (code "79") (name "Net-(X3B-KL)") (class "Default")
      (node (ref "C11") (pin "1") (pinfunction "1_1") (pintype "passive"))
      (node (ref "C12") (pin "1") (pinfunction "1_1") (pintype "passive"))
      (node (ref "C17") (pin "1") (pinfunction "1_1") (pintype "passive"))
      (node (ref "L3") (pin "1") (pinfunction "1_1") (pintype "passive"))
      (node (ref "X3") (pin "2") (pinfunction "KL_2") (pintype "passive"))
    )
    (net (code "80") (name "VCC") (class "Default")
      (node (ref "C1") (pin "+") (pinfunction "+_+") (pintype "passive"))
      (node (ref "C2") (pin "1") (pinfunction "1_1") (pintype "passive"))
      (node (ref "C3") (pin "1") (pinfunction "1_1") (pintype "passive"))
      (node (ref "C4") (pin "+") (pinfunction "+_+") (pintype "passive"))
      (node (ref "C5") (pin "1") (pinfunction "1_1") (pintype "passive"))
      (node (ref "C6") (pin "1") (pinfunction "1_1") (pintype "passive"))
      (node (ref "JP4") (pin "1") (pinfunction "1_1") (pintype "passive"))
      (node (ref "R27") (pin "2") (pinfunction "2_2") (pintype "passive"))
      (node (ref "R28") (pin "2") (pinfunction "2_2") (pintype "passive"))
      (node (ref "R29") (pin "2") (pinfunction "2_2") (pintype "passive"))
      (node (ref "R34") (pin "2") (pinfunction "2_2") (pintype "passive"))
      (node (ref "R35") (pin "2") (pinfunction "2_2") (pintype "passive"))
      (node (ref "R37") (pin "2") (pinfunction "2_2") (pintype "passive"))
      (node (ref "R38") (pin "2") (pinfunction "2_2") (pintype "passive"))
      (node (ref "U1") (pin "18") (pinfunction "PVCC_2_18") (pintype "power_in"))
      (node (ref "U1") (pin "19") (pinfunction "PVCC_3_19") (pintype "power_in"))
      (node (ref "U1") (pin "31") (pinfunction "PVCC_4_31") (pintype "power_in"))
      (node (ref "U1") (pin "32") (pinfunction "PVCC_32") (pintype "power_in"))
      (node (ref "X1") (pin "1") (pinfunction "KL_1") (pintype "passive"))
    )
    (net (code "81") (name "unconnected-(S1-P1-Pad4)") (class "Default")
      (node (ref "S1") (pin "4") (pinfunction "P1_4") (pintype "passive"))
    )
    (net (code "82") (name "unconnected-(S1-S1-Pad2)") (class "Default")
      (node (ref "S1") (pin "2") (pinfunction "S1_2") (pintype "passive"))
    )
    (net (code "83") (name "unconnected-(S2-P1-Pad4)") (class "Default")
      (node (ref "S2") (pin "4") (pinfunction "P1_4") (pintype "passive"))
    )
    (net (code "84") (name "unconnected-(S2-S1-Pad2)") (class "Default")
      (node (ref "S2") (pin "2") (pinfunction "S1_2") (pintype "passive"))
    )
    (net (code "85") (name "unconnected-(U1-SYNC-Pad16)") (class "Default")
      (node (ref "U1") (pin "16") (pinfunction "SYNC_16") (pintype "bidirectional"))
    )
    (net (code "86") (name "unconnected-(U2C-V+-Pad8)") (class "Default")
      (node (ref "U2") (pin "8") (pinfunction "V+_8") (pintype "power_in"))
    )
    (net (code "87") (name "unconnected-(U3C-V+-Pad8)") (class "Default")
      (node (ref "U3") (pin "8") (pinfunction "V+_8") (pintype "power_in"))
    )
  )
)
